# Onion-Omega2-BLE-Pro-Expansion.net
KiCad netlist of a schematic drawn in EAGLE
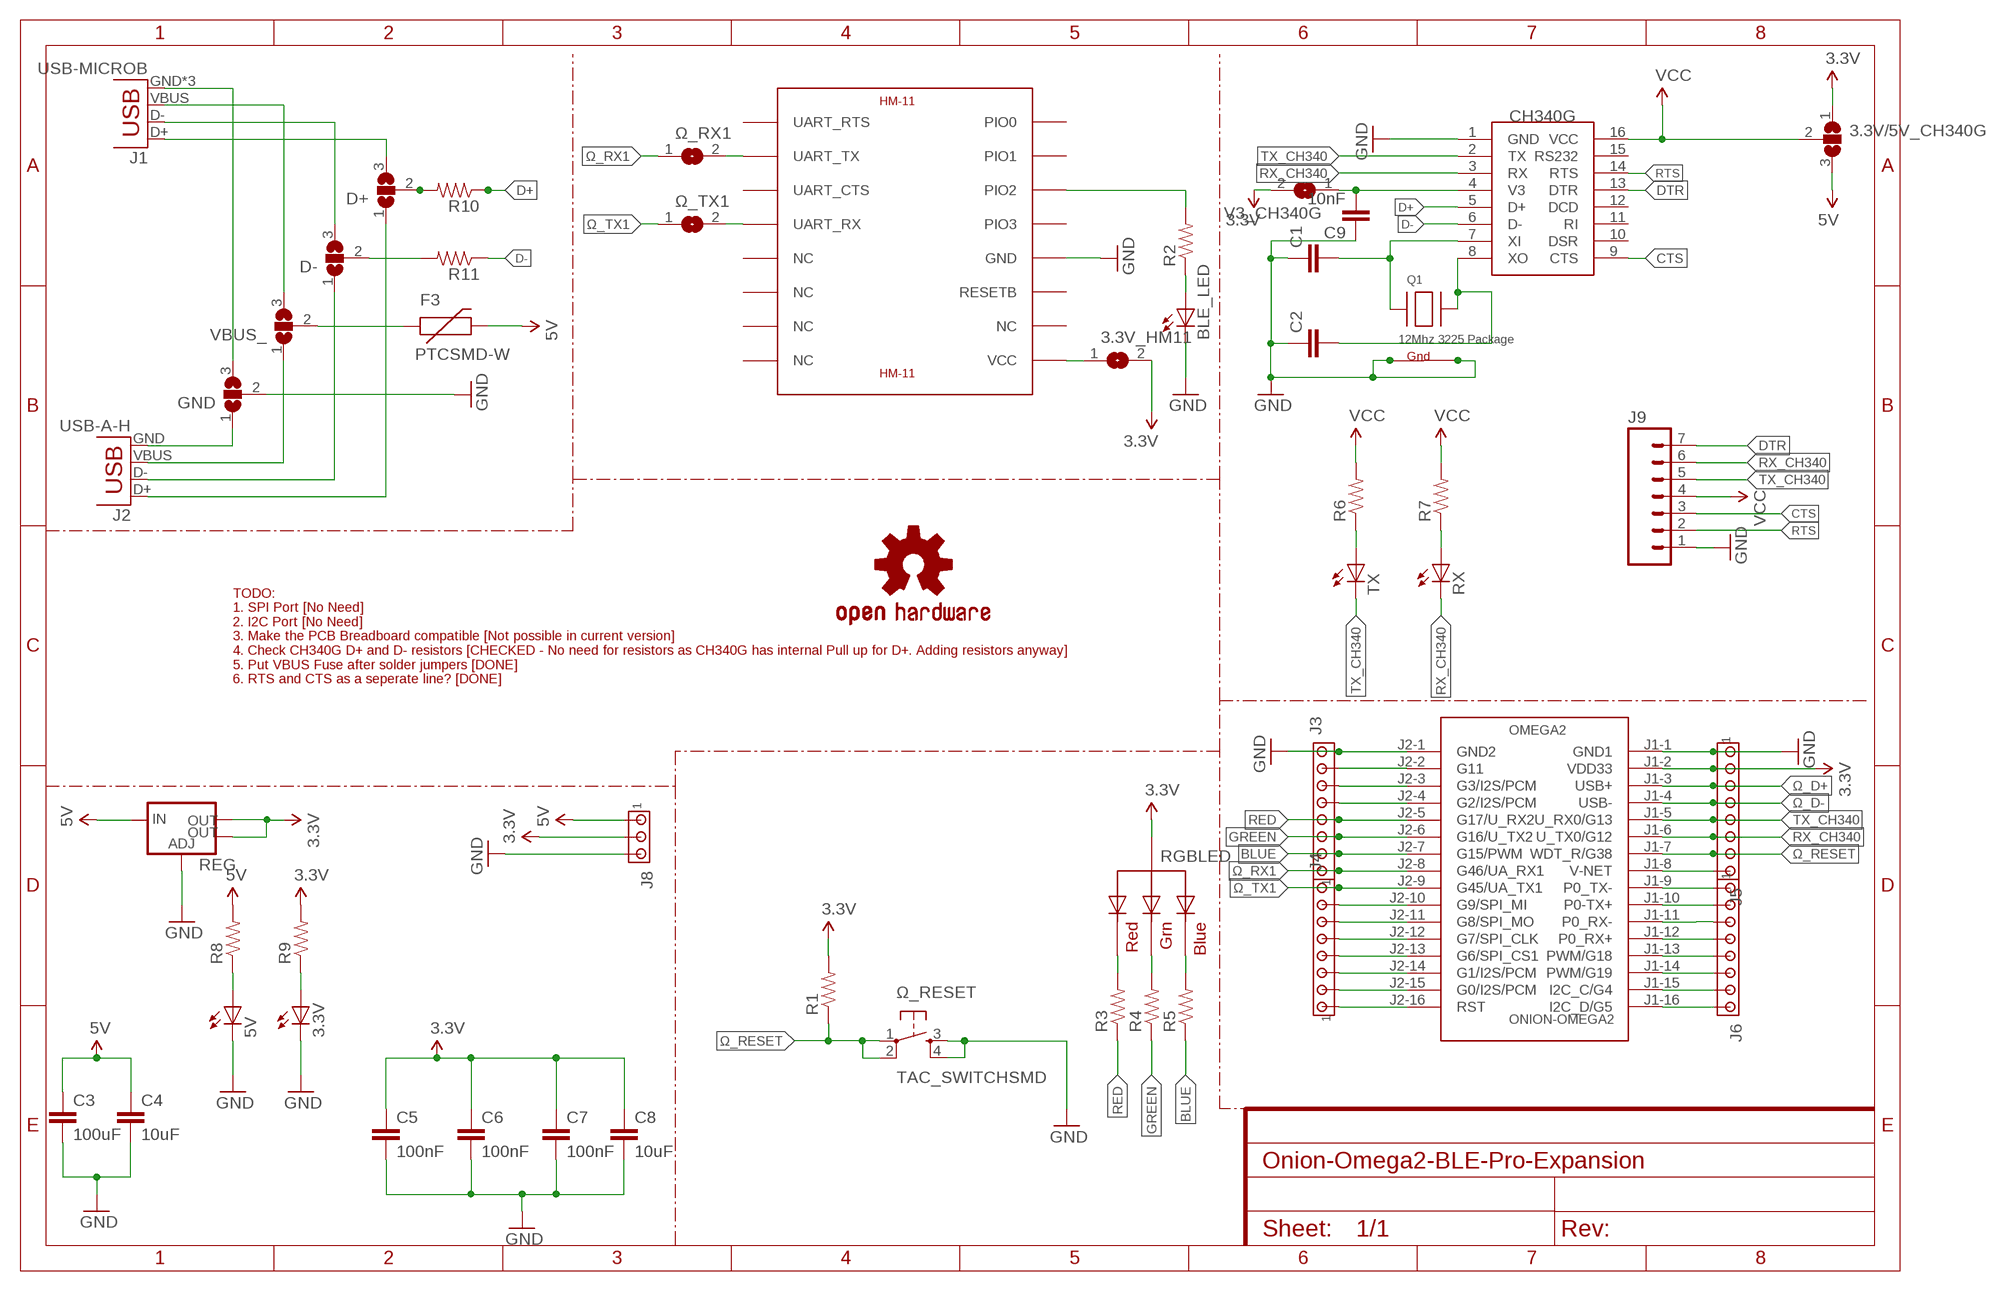
[diagram p0: schematic, sheet 1]

(export (version "E")
  (design (tool "Eeschema 10.0.6"))
  (components
    (comp (ref "3.3V")
      (value "LEDCHIPLED_1206")
      (footprint "eagle-import:CHIPLED_1206")
      (libsource (lib "eagle-import") (part "LEDCHIPLED_1206"))
    )
    (comp (ref "3.3V/5V_CH340G")
      (value "SJ2W")
      (footprint "eagle-import:SJ_2")
      (libsource (lib "eagle-import") (part "SJ2W"))
    )
    (comp (ref "3.3V_HM11")
      (value "SJ")
      (footprint "eagle-import:SJ")
      (libsource (lib "eagle-import") (part "SJ"))
    )
    (comp (ref "5V")
      (value "LEDCHIPLED_1206")
      (footprint "eagle-import:CHIPLED_1206")
      (libsource (lib "eagle-import") (part "LEDCHIPLED_1206"))
    )
    (comp (ref "BLE_LED")
      (value "LEDCHIPLED_1206")
      (footprint "eagle-import:CHIPLED_1206")
      (libsource (lib "eagle-import") (part "LEDCHIPLED_1206"))
    )
    (comp (ref "C1")
      (value "CAP1206")
      (footprint "eagle-import:1206")
      (libsource (lib "eagle-import") (part "CAP1206"))
    )
    (comp (ref "C2")
      (value "CAP1206")
      (footprint "eagle-import:1206")
      (libsource (lib "eagle-import") (part "CAP1206"))
    )
    (comp (ref "C3")
      (value "100uF")
      (footprint "eagle-import:1206")
      (libsource (lib "eagle-import") (part "CAP1206"))
    )
    (comp (ref "C4")
      (value "10uF")
      (footprint "eagle-import:1206")
      (libsource (lib "eagle-import") (part "CAP1206"))
    )
    (comp (ref "C5")
      (value "100nF")
      (footprint "eagle-import:1206")
      (libsource (lib "eagle-import") (part "CAP1206"))
    )
    (comp (ref "C6")
      (value "100nF")
      (footprint "eagle-import:1206")
      (libsource (lib "eagle-import") (part "CAP1206"))
    )
    (comp (ref "C7")
      (value "100nF")
      (footprint "eagle-import:1206")
      (libsource (lib "eagle-import") (part "CAP1206"))
    )
    (comp (ref "C8")
      (value "10uF")
      (footprint "eagle-import:1206")
      (libsource (lib "eagle-import") (part "CAP1206"))
    )
    (comp (ref "C9")
      (value "10nF")
      (footprint "eagle-import:1206")
      (libsource (lib "eagle-import") (part "CAP1206"))
    )
    (comp (ref "D+")
      (value "SJ2W")
      (footprint "eagle-import:SJ_2")
      (libsource (lib "eagle-import") (part "SJ2W"))
    )
    (comp (ref "D-")
      (value "SJ2W")
      (footprint "eagle-import:SJ_2")
      (libsource (lib "eagle-import") (part "SJ2W"))
    )
    (comp (ref "F3")
      (value "PTCSMD-W")
      (footprint "eagle-import:PTC-1206-WIDE")
      (libsource (lib "eagle-import") (part "PTCSMD-W"))
    )
    (comp (ref "GND")
      (value "SJ2W")
      (footprint "eagle-import:SJ_2")
      (libsource (lib "eagle-import") (part "SJ2W"))
    )
    (comp (ref "J1")
      (value "USB-MICROB")
      (footprint "eagle-import:USB-MICROB")
      (libsource (lib "eagle-import") (part "USB-MICROB"))
    )
    (comp (ref "J2")
      (value "USB-A-H")
      (footprint "eagle-import:USB-A-H")
      (libsource (lib "eagle-import") (part "USB-A-H"))
    )
    (comp (ref "J3")
      (value "MTA08-100")
      (footprint "eagle-import:10X08MTA")
      (libsource (lib "eagle-import") (part "MTA08-100"))
    )
    (comp (ref "J4")
      (value "MTA08-100")
      (footprint "eagle-import:10X08MTA")
      (libsource (lib "eagle-import") (part "MTA08-100"))
    )
    (comp (ref "J5")
      (value "MTA08-100")
      (footprint "eagle-import:10X08MTA")
      (libsource (lib "eagle-import") (part "MTA08-100"))
    )
    (comp (ref "J6")
      (value "MTA08-100")
      (footprint "eagle-import:10X08MTA")
      (libsource (lib "eagle-import") (part "MTA08-100"))
    )
    (comp (ref "J8")
      (value "MTA03-100")
      (footprint "eagle-import:10X03MTA")
      (libsource (lib "eagle-import") (part "MTA03-100"))
    )
    (comp (ref "J9")
      (value "M07SMD")
      (footprint "eagle-import:1X07-SMD-FEMALE-V2")
      (libsource (lib "eagle-import") (part "M07SMD"))
    )
    (comp (ref "LOGO1")
      (value "OSHW-LOGOMINI")
      (footprint "eagle-import:OSHW-LOGO-MINI")
      (libsource (lib "eagle-import") (part "OSHW-LOGOMINI"))
    )
    (comp (ref "OMEGA2")
      (value "ONION-OMEGA2")
      (footprint "eagle-import:ONION-2MM-2X16")
      (libsource (lib "eagle-import") (part "ONION-OMEGA2"))
    )
    (comp (ref "Q1")
      (value "12Mhz 3225 Package")
      (footprint "eagle-import:NX3225")
      (libsource (lib "eagle-import") (part "XTAL-4-3225"))
    )
    (comp (ref "R1")
      (value "RESISTOR1206")
      (footprint "eagle-import:1206")
      (libsource (lib "eagle-import") (part "RESISTOR1206"))
    )
    (comp (ref "R2")
      (value "RESISTOR1206")
      (footprint "eagle-import:1206")
      (libsource (lib "eagle-import") (part "RESISTOR1206"))
    )
    (comp (ref "R3")
      (value "RESISTOR1206")
      (footprint "eagle-import:1206")
      (libsource (lib "eagle-import") (part "RESISTOR1206"))
    )
    (comp (ref "R4")
      (value "RESISTOR1206")
      (footprint "eagle-import:1206")
      (libsource (lib "eagle-import") (part "RESISTOR1206"))
    )
    (comp (ref "R5")
      (value "RESISTOR1206")
      (footprint "eagle-import:1206")
      (libsource (lib "eagle-import") (part "RESISTOR1206"))
    )
    (comp (ref "R6")
      (value "RESISTOR1206")
      (footprint "eagle-import:1206")
      (libsource (lib "eagle-import") (part "RESISTOR1206"))
    )
    (comp (ref "R7")
      (value "RESISTOR1206")
      (footprint "eagle-import:1206")
      (libsource (lib "eagle-import") (part "RESISTOR1206"))
    )
    (comp (ref "R8")
      (value "RESISTOR1206")
      (footprint "eagle-import:1206")
      (libsource (lib "eagle-import") (part "RESISTOR1206"))
    )
    (comp (ref "R9")
      (value "RESISTOR1206")
      (footprint "eagle-import:1206")
      (libsource (lib "eagle-import") (part "RESISTOR1206"))
    )
    (comp (ref "R10")
      (value "RESISTOR0805-RES")
      (footprint "eagle-import:0805")
      (libsource (lib "eagle-import") (part "RESISTOR0805-RES"))
    )
    (comp (ref "R11")
      (value "RESISTOR0805-RES")
      (footprint "eagle-import:0805")
      (libsource (lib "eagle-import") (part "RESISTOR0805-RES"))
    )
    (comp (ref "REG")
      (value "V_REG_LM1117SOT223")
      (footprint "eagle-import:SOT223")
      (libsource (lib "eagle-import") (part "V_REG_LM1117SOT223"))
    )
    (comp (ref "RGBLED")
      (value "RGBLED_CA-PIRANHA")
      (footprint "eagle-import:PIRANHA5MM")
      (libsource (lib "eagle-import") (part "RGBLED_CA-PIRANHA"))
    )
    (comp (ref "RX")
      (value "LEDCHIPLED_1206")
      (footprint "eagle-import:CHIPLED_1206")
      (libsource (lib "eagle-import") (part "LEDCHIPLED_1206"))
    )
    (comp (ref "TX")
      (value "LEDCHIPLED_1206")
      (footprint "eagle-import:CHIPLED_1206")
      (libsource (lib "eagle-import") (part "LEDCHIPLED_1206"))
    )
    (comp (ref "U$1")
      (value "CH340G")
      (footprint "eagle-import:SOIC16")
      (libsource (lib "eagle-import") (part "CH340G"))
    )
    (comp (ref "U$2")
      (value "HM-11")
      (footprint "eagle-import:HM-11")
      (libsource (lib "eagle-import") (part "HM-11"))
    )
    (comp (ref "V3_CH340G")
      (value "SJ")
      (footprint "eagle-import:SJ")
      (libsource (lib "eagle-import") (part "SJ"))
    )
    (comp (ref "VBUS_")
      (value "SJ2W")
      (footprint "eagle-import:SJ_2")
      (libsource (lib "eagle-import") (part "SJ2W"))
    )
    (comp (ref "Ω_RESET")
      (value "TAC_SWITCHSMD")
      (footprint "eagle-import:TACTILE-SWITCH-SMD")
      (libsource (lib "eagle-import") (part "TAC_SWITCHSMD"))
    )
    (comp (ref "Ω_RX1")
      (value "SJ")
      (footprint "eagle-import:SJ")
      (libsource (lib "eagle-import") (part "SJ"))
    )
    (comp (ref "Ω_TX1")
      (value "SJ")
      (footprint "eagle-import:SJ")
      (libsource (lib "eagle-import") (part "SJ"))
    )
  )
  (nets
    (net (code "1") (name "3.3V") (class "Default")
      (node (ref "3.3V/5V_CH340G") (pin "1") (pinfunction "1_1") (pintype "passive"))
      (node (ref "3.3V_HM11") (pin "2") (pinfunction "2_2") (pintype "passive"))
      (node (ref "C5") (pin "1") (pinfunction "1_1") (pintype "passive"))
      (node (ref "C6") (pin "1") (pinfunction "1_1") (pintype "passive"))
      (node (ref "C7") (pin "1") (pinfunction "1_1") (pintype "passive"))
      (node (ref "C8") (pin "1") (pinfunction "1_1") (pintype "passive"))
      (node (ref "J5") (pin "2") (pinfunction "2_2") (pintype "passive"))
      (node (ref "J8") (pin "2") (pinfunction "2_2") (pintype "passive"))
      (node (ref "OMEGA2") (pin "J1-2") (pinfunction "VDD33_J1-2") (pintype "bidirectional"))
      (node (ref "R1") (pin "2") (pinfunction "2_2") (pintype "passive"))
      (node (ref "R9") (pin "2") (pinfunction "2_2") (pintype "passive"))
      (node (ref "REG") (pin "2") (pinfunction "OUT_2") (pintype "output"))
      (node (ref "REG") (pin "4") (pinfunction "OUT_4") (pintype "output"))
      (node (ref "RGBLED") (pin "4") (pinfunction "VCC_4") (pintype "bidirectional"))
      (node (ref "V3_CH340G") (pin "2") (pinfunction "2_2") (pintype "passive"))
    )
    (net (code "2") (name "5V") (class "Default")
      (node (ref "3.3V/5V_CH340G") (pin "3") (pinfunction "3_3") (pintype "passive"))
      (node (ref "C3") (pin "1") (pinfunction "1_1") (pintype "passive"))
      (node (ref "C4") (pin "1") (pinfunction "1_1") (pintype "passive"))
      (node (ref "F3") (pin "2") (pinfunction "2_2") (pintype "bidirectional"))
      (node (ref "J8") (pin "1") (pinfunction "1_1") (pintype "passive"))
      (node (ref "R8") (pin "2") (pinfunction "2_2") (pintype "passive"))
      (node (ref "REG") (pin "3") (pinfunction "IN_3") (pintype "input"))
    )
    (net (code "3") (name "BLUE") (class "Default")
      (node (ref "J3") (pin "2") (pinfunction "2_2") (pintype "passive"))
      (node (ref "OMEGA2") (pin "J2-7") (pinfunction "G15/PWM_J2-7") (pintype "bidirectional"))
      (node (ref "R5") (pin "1") (pinfunction "1_1") (pintype "passive"))
    )
    (net (code "4") (name "CTS") (class "Default")
      (node (ref "J9") (pin "3") (pinfunction "3_3") (pintype "passive"))
      (node (ref "U$1") (pin "9") (pinfunction "CTS_9") (pintype "bidirectional"))
    )
    (net (code "5") (name "D+") (class "Default")
      (node (ref "R10") (pin "1") (pinfunction "1_1") (pintype "passive"))
      (node (ref "U$1") (pin "5") (pinfunction "D+_5") (pintype "bidirectional"))
    )
    (net (code "6") (name "D-") (class "Default")
      (node (ref "R11") (pin "1") (pinfunction "1_1") (pintype "passive"))
      (node (ref "U$1") (pin "6") (pinfunction "D-_6") (pintype "bidirectional"))
    )
    (net (code "7") (name "DTR") (class "Default")
      (node (ref "J9") (pin "7") (pinfunction "7_7") (pintype "passive"))
      (node (ref "U$1") (pin "13") (pinfunction "DTR_13") (pintype "bidirectional"))
    )
    (net (code "8") (name "GND") (class "Default")
      (node (ref "3.3V") (pin "C") (pinfunction "C_C") (pintype "passive"))
      (node (ref "5V") (pin "C") (pinfunction "C_C") (pintype "passive"))
      (node (ref "BLE_LED") (pin "C") (pinfunction "C_C") (pintype "passive"))
      (node (ref "C1") (pin "1") (pinfunction "1_1") (pintype "passive"))
      (node (ref "C2") (pin "1") (pinfunction "1_1") (pintype "passive"))
      (node (ref "C3") (pin "2") (pinfunction "2_2") (pintype "passive"))
      (node (ref "C4") (pin "2") (pinfunction "2_2") (pintype "passive"))
      (node (ref "C5") (pin "2") (pinfunction "2_2") (pintype "passive"))
      (node (ref "C6") (pin "2") (pinfunction "2_2") (pintype "passive"))
      (node (ref "C7") (pin "2") (pinfunction "2_2") (pintype "passive"))
      (node (ref "C8") (pin "2") (pinfunction "2_2") (pintype "passive"))
      (node (ref "C9") (pin "1") (pinfunction "1_1") (pintype "passive"))
      (node (ref "GND") (pin "2") (pinfunction "2_2") (pintype "passive"))
      (node (ref "J3") (pin "8") (pinfunction "8_8") (pintype "passive"))
      (node (ref "J5") (pin "1") (pinfunction "1_1") (pintype "passive"))
      (node (ref "J8") (pin "3") (pinfunction "3_3") (pintype "passive"))
      (node (ref "J9") (pin "1") (pinfunction "1_1") (pintype "passive"))
      (node (ref "OMEGA2") (pin "J1-1") (pinfunction "GND1_J1-1") (pintype "bidirectional"))
      (node (ref "OMEGA2") (pin "J2-1") (pinfunction "GND2_J2-1") (pintype "bidirectional"))
      (node (ref "Q1") (pin "2") (pinfunction "G2_2") (pintype "power_in"))
      (node (ref "Q1") (pin "4") (pinfunction "G1_4") (pintype "power_in"))
      (node (ref "REG") (pin "1") (pinfunction "ADJ_1") (pintype "input"))
      (node (ref "U$1") (pin "1") (pinfunction "GND_1") (pintype "bidirectional"))
      (node (ref "U$2") (pin "GND") (pinfunction "GND_GND") (pintype "bidirectional"))
      (node (ref "Ω_RESET") (pin "3") (pinfunction "3_3") (pintype "passive"))
      (node (ref "Ω_RESET") (pin "4") (pinfunction "4_4") (pintype "passive"))
    )
    (net (code "9") (name "GREEN") (class "Default")
      (node (ref "J3") (pin "3") (pinfunction "3_3") (pintype "passive"))
      (node (ref "OMEGA2") (pin "J2-6") (pinfunction "G16/U_TX2_J2-6") (pintype "bidirectional"))
      (node (ref "R4") (pin "1") (pinfunction "1_1") (pintype "passive"))
    )
    (net (code "10") (name "Net-(3.3V-PadA)") (class "Default")
      (node (ref "3.3V") (pin "A") (pinfunction "A_A") (pintype "passive"))
      (node (ref "R9") (pin "1") (pinfunction "1_1") (pintype "passive"))
    )
    (net (code "11") (name "Net-(3.3V_HM11-Pad1)") (class "Default")
      (node (ref "3.3V_HM11") (pin "1") (pinfunction "1_1") (pintype "passive"))
      (node (ref "U$2") (pin "VCC") (pinfunction "VCC_VCC") (pintype "bidirectional"))
    )
    (net (code "12") (name "Net-(5V-PadA)") (class "Default")
      (node (ref "5V") (pin "A") (pinfunction "A_A") (pintype "passive"))
      (node (ref "R8") (pin "1") (pinfunction "1_1") (pintype "passive"))
    )
    (net (code "13") (name "Net-(BLE_LED-PadA)") (class "Default")
      (node (ref "BLE_LED") (pin "A") (pinfunction "A_A") (pintype "passive"))
      (node (ref "R2") (pin "1") (pinfunction "1_1") (pintype "passive"))
    )
    (net (code "14") (name "Net-(D+-Pad1)") (class "Default")
      (node (ref "D+") (pin "1") (pinfunction "1_1") (pintype "passive"))
      (node (ref "J2") (pin "D+") (pinfunction "D+_D+") (pintype "bidirectional"))
    )
    (net (code "15") (name "Net-(D+-Pad2)") (class "Default")
      (node (ref "D+") (pin "2") (pinfunction "2_2") (pintype "passive"))
      (node (ref "R10") (pin "2") (pinfunction "2_2") (pintype "passive"))
    )
    (net (code "16") (name "Net-(D+-Pad3)") (class "Default")
      (node (ref "D+") (pin "3") (pinfunction "3_3") (pintype "passive"))
      (node (ref "J1") (pin "D+") (pinfunction "D+_D+") (pintype "bidirectional"))
    )
    (net (code "17") (name "Net-(D--Pad1)") (class "Default")
      (node (ref "D-") (pin "1") (pinfunction "1_1") (pintype "passive"))
      (node (ref "J2") (pin "D-") (pinfunction "D-_D-") (pintype "bidirectional"))
    )
    (net (code "18") (name "Net-(D--Pad2)") (class "Default")
      (node (ref "D-") (pin "2") (pinfunction "2_2") (pintype "passive"))
      (node (ref "R11") (pin "2") (pinfunction "2_2") (pintype "passive"))
    )
    (net (code "19") (name "Net-(D--Pad3)") (class "Default")
      (node (ref "D-") (pin "3") (pinfunction "3_3") (pintype "passive"))
      (node (ref "J1") (pin "D-") (pinfunction "D-_D-") (pintype "bidirectional"))
    )
    (net (code "20") (name "Net-(F3-Pad1)") (class "Default")
      (node (ref "F3") (pin "1") (pinfunction "1_1") (pintype "bidirectional"))
      (node (ref "VBUS_") (pin "2") (pinfunction "2_2") (pintype "passive"))
    )
    (net (code "21") (name "Net-(GND-Pad1)") (class "Default")
      (node (ref "GND") (pin "1") (pinfunction "1_1") (pintype "passive"))
      (node (ref "J2") (pin "GND") (pinfunction "GND_GND") (pintype "bidirectional"))
    )
    (net (code "22") (name "Net-(GND-Pad3)") (class "Default")
      (node (ref "GND") (pin "3") (pinfunction "3_3") (pintype "passive"))
      (node (ref "J1") (pin "GND") (pinfunction "GND_GND") (pintype "bidirectional"))
      (node (ref "J1") (pin "MT1") (pinfunction "GND_MT1") (pintype "bidirectional"))
      (node (ref "J1") (pin "MT2") (pinfunction "GND_MT2") (pintype "bidirectional"))
    )
    (net (code "23") (name "Net-(J1-PadVBUS)") (class "Default")
      (node (ref "J1") (pin "VBUS") (pinfunction "VBUS_VBUS") (pintype "bidirectional"))
      (node (ref "VBUS_") (pin "3") (pinfunction "3_3") (pintype "passive"))
    )
    (net (code "24") (name "Net-(J2-PadVBUS)") (class "Default")
      (node (ref "J2") (pin "VBUS") (pinfunction "VBUS_VBUS") (pintype "bidirectional"))
      (node (ref "VBUS_") (pin "1") (pinfunction "1_1") (pintype "passive"))
    )
    (net (code "25") (name "Net-(OMEGA2-G0{slash}I2S{slash}PCM)") (class "Default")
      (node (ref "J4") (pin "2") (pinfunction "2_2") (pintype "passive"))
      (node (ref "OMEGA2") (pin "J2-15") (pinfunction "G0/I2S/PCM_J2-15") (pintype "bidirectional"))
    )
    (net (code "26") (name "Net-(OMEGA2-G1{slash}I2S{slash}PCM)") (class "Default")
      (node (ref "J4") (pin "3") (pinfunction "3_3") (pintype "passive"))
      (node (ref "OMEGA2") (pin "J2-14") (pinfunction "G1/I2S/PCM_J2-14") (pintype "bidirectional"))
    )
    (net (code "27") (name "Net-(OMEGA2-G2{slash}I2S{slash}PCM)") (class "Default")
      (node (ref "J3") (pin "5") (pinfunction "5_5") (pintype "passive"))
      (node (ref "OMEGA2") (pin "J2-4") (pinfunction "G2/I2S/PCM_J2-4") (pintype "bidirectional"))
    )
    (net (code "28") (name "Net-(OMEGA2-G3{slash}I2S{slash}PCM)") (class "Default")
      (node (ref "J3") (pin "6") (pinfunction "6_6") (pintype "passive"))
      (node (ref "OMEGA2") (pin "J2-3") (pinfunction "G3/I2S/PCM_J2-3") (pintype "bidirectional"))
    )
    (net (code "29") (name "Net-(OMEGA2-G6{slash}SPI_CS1)") (class "Default")
      (node (ref "J4") (pin "4") (pinfunction "4_4") (pintype "passive"))
      (node (ref "OMEGA2") (pin "J2-13") (pinfunction "G6/SPI_CS1_J2-13") (pintype "bidirectional"))
    )
    (net (code "30") (name "Net-(OMEGA2-G7{slash}SPI_CLK)") (class "Default")
      (node (ref "J4") (pin "5") (pinfunction "5_5") (pintype "passive"))
      (node (ref "OMEGA2") (pin "J2-12") (pinfunction "G7/SPI_CLK_J2-12") (pintype "bidirectional"))
    )
    (net (code "31") (name "Net-(OMEGA2-G8{slash}SPI_MO)") (class "Default")
      (node (ref "J4") (pin "6") (pinfunction "6_6") (pintype "passive"))
      (node (ref "OMEGA2") (pin "J2-11") (pinfunction "G8/SPI_MO_J2-11") (pintype "bidirectional"))
    )
    (net (code "32") (name "Net-(OMEGA2-G9{slash}SPI_MI)") (class "Default")
      (node (ref "J4") (pin "7") (pinfunction "7_7") (pintype "passive"))
      (node (ref "OMEGA2") (pin "J2-10") (pinfunction "G9/SPI_MI_J2-10") (pintype "bidirectional"))
    )
    (net (code "33") (name "Net-(OMEGA2-G11)") (class "Default")
      (node (ref "J3") (pin "7") (pinfunction "7_7") (pintype "passive"))
      (node (ref "OMEGA2") (pin "J2-2") (pinfunction "G11_J2-2") (pintype "bidirectional"))
    )
    (net (code "34") (name "Net-(OMEGA2-I2C_C{slash}G4)") (class "Default")
      (node (ref "J6") (pin "7") (pinfunction "7_7") (pintype "passive"))
      (node (ref "OMEGA2") (pin "J1-15") (pinfunction "I2C_C/G4_J1-15") (pintype "bidirectional"))
    )
    (net (code "35") (name "Net-(OMEGA2-I2C_D{slash}G5)") (class "Default")
      (node (ref "J6") (pin "8") (pinfunction "8_8") (pintype "passive"))
      (node (ref "OMEGA2") (pin "J1-16") (pinfunction "I2C_D/G5_J1-16") (pintype "bidirectional"))
    )
    (net (code "36") (name "Net-(OMEGA2-P0-TX+)") (class "Default")
      (node (ref "J6") (pin "2") (pinfunction "2_2") (pintype "passive"))
      (node (ref "OMEGA2") (pin "J1-10") (pinfunction "P0-TX+_J1-10") (pintype "bidirectional"))
    )
    (net (code "37") (name "Net-(OMEGA2-P0_RX+)") (class "Default")
      (node (ref "J6") (pin "4") (pinfunction "4_4") (pintype "passive"))
      (node (ref "OMEGA2") (pin "J1-12") (pinfunction "P0_RX+_J1-12") (pintype "bidirectional"))
    )
    (net (code "38") (name "Net-(OMEGA2-P0_RX-)") (class "Default")
      (node (ref "J6") (pin "3") (pinfunction "3_3") (pintype "passive"))
      (node (ref "OMEGA2") (pin "J1-11") (pinfunction "P0_RX-_J1-11") (pintype "bidirectional"))
    )
    (net (code "39") (name "Net-(OMEGA2-P0_TX-)") (class "Default")
      (node (ref "J6") (pin "1") (pinfunction "1_1") (pintype "passive"))
      (node (ref "OMEGA2") (pin "J1-9") (pinfunction "P0_TX-_J1-9") (pintype "bidirectional"))
    )
    (net (code "40") (name "Net-(OMEGA2-PWM{slash}G18)") (class "Default")
      (node (ref "J6") (pin "5") (pinfunction "5_5") (pintype "passive"))
      (node (ref "OMEGA2") (pin "J1-13") (pinfunction "PWM/G18_J1-13") (pintype "bidirectional"))
    )
    (net (code "41") (name "Net-(OMEGA2-PWM{slash}G19)") (class "Default")
      (node (ref "J6") (pin "6") (pinfunction "6_6") (pintype "passive"))
      (node (ref "OMEGA2") (pin "J1-14") (pinfunction "PWM/G19_J1-14") (pintype "bidirectional"))
    )
    (net (code "42") (name "Net-(OMEGA2-RST)") (class "Default")
      (node (ref "J4") (pin "1") (pinfunction "1_1") (pintype "passive"))
      (node (ref "OMEGA2") (pin "J2-16") (pinfunction "RST_J2-16") (pintype "bidirectional"))
    )
    (net (code "43") (name "Net-(OMEGA2-V-NET)") (class "Default")
      (node (ref "J5") (pin "8") (pinfunction "8_8") (pintype "passive"))
      (node (ref "OMEGA2") (pin "J1-8") (pinfunction "V-NET_J1-8") (pintype "bidirectional"))
    )
    (net (code "44") (name "Net-(Q1-X1)") (class "Default")
      (node (ref "C1") (pin "2") (pinfunction "2_2") (pintype "passive"))
      (node (ref "Q1") (pin "1") (pinfunction "X1_1") (pintype "bidirectional"))
      (node (ref "U$1") (pin "7") (pinfunction "XI_7") (pintype "bidirectional"))
    )
    (net (code "45") (name "Net-(Q1-X2)") (class "Default")
      (node (ref "C2") (pin "2") (pinfunction "2_2") (pintype "passive"))
      (node (ref "Q1") (pin "3") (pinfunction "X2_3") (pintype "bidirectional"))
      (node (ref "U$1") (pin "8") (pinfunction "XO_8") (pintype "bidirectional"))
    )
    (net (code "46") (name "Net-(R2-Pad2)") (class "Default")
      (node (ref "R2") (pin "2") (pinfunction "2_2") (pintype "passive"))
      (node (ref "U$2") (pin "PIO2") (pinfunction "PIO2_PIO2") (pintype "bidirectional"))
    )
    (net (code "47") (name "Net-(R6-Pad1)") (class "Default")
      (node (ref "R6") (pin "1") (pinfunction "1_1") (pintype "passive"))
      (node (ref "TX") (pin "A") (pinfunction "A_A") (pintype "passive"))
    )
    (net (code "48") (name "Net-(R7-Pad1)") (class "Default")
      (node (ref "R7") (pin "1") (pinfunction "1_1") (pintype "passive"))
      (node (ref "RX") (pin "A") (pinfunction "A_A") (pintype "passive"))
    )
    (net (code "49") (name "Net-(RGBLED-BLUE)") (class "Default")
      (node (ref "R5") (pin "2") (pinfunction "2_2") (pintype "passive"))
      (node (ref "RGBLED") (pin "1") (pinfunction "BLUE_1") (pintype "bidirectional"))
    )
    (net (code "50") (name "Net-(RGBLED-GREEN)") (class "Default")
      (node (ref "R4") (pin "2") (pinfunction "2_2") (pintype "passive"))
      (node (ref "RGBLED") (pin "3") (pinfunction "GREEN_3") (pintype "bidirectional"))
    )
    (net (code "51") (name "Net-(RGBLED-RED)") (class "Default")
      (node (ref "R3") (pin "2") (pinfunction "2_2") (pintype "passive"))
      (node (ref "RGBLED") (pin "2") (pinfunction "RED_2") (pintype "bidirectional"))
    )
    (net (code "52") (name "Net-(U$1-V3)") (class "Default")
      (node (ref "C9") (pin "2") (pinfunction "2_2") (pintype "passive"))
      (node (ref "U$1") (pin "4") (pinfunction "V3_4") (pintype "bidirectional"))
      (node (ref "V3_CH340G") (pin "1") (pinfunction "1_1") (pintype "passive"))
    )
    (net (code "53") (name "Net-(U$2-PadUART_RX)") (class "Default")
      (node (ref "U$2") (pin "UART_RX") (pinfunction "UART_RX_UART_RX") (pintype "bidirectional"))
      (node (ref "Ω_TX1") (pin "2") (pinfunction "2_2") (pintype "passive"))
    )
    (net (code "54") (name "Net-(U$2-PadUART_TX)") (class "Default")
      (node (ref "U$2") (pin "UART_TX") (pinfunction "UART_TX_UART_TX") (pintype "bidirectional"))
      (node (ref "Ω_RX1") (pin "2") (pinfunction "2_2") (pintype "passive"))
    )
    (net (code "55") (name "RED") (class "Default")
      (node (ref "J3") (pin "4") (pinfunction "4_4") (pintype "passive"))
      (node (ref "OMEGA2") (pin "J2-5") (pinfunction "G17/U_RX2_J2-5") (pintype "bidirectional"))
      (node (ref "R3") (pin "1") (pinfunction "1_1") (pintype "passive"))
    )
    (net (code "56") (name "RTS") (class "Default")
      (node (ref "J9") (pin "2") (pinfunction "2_2") (pintype "passive"))
      (node (ref "U$1") (pin "14") (pinfunction "RTS_14") (pintype "bidirectional"))
    )
    (net (code "57") (name "RX_CH340") (class "Default")
      (node (ref "J5") (pin "6") (pinfunction "6_6") (pintype "passive"))
      (node (ref "J9") (pin "6") (pinfunction "6_6") (pintype "passive"))
      (node (ref "OMEGA2") (pin "J1-6") (pinfunction "U_TX0/G12_J1-6") (pintype "bidirectional"))
      (node (ref "RX") (pin "C") (pinfunction "C_C") (pintype "passive"))
      (node (ref "U$1") (pin "3") (pinfunction "RX_3") (pintype "bidirectional"))
    )
    (net (code "58") (name "TX_CH340") (class "Default")
      (node (ref "J5") (pin "5") (pinfunction "5_5") (pintype "passive"))
      (node (ref "J9") (pin "5") (pinfunction "5_5") (pintype "passive"))
      (node (ref "OMEGA2") (pin "J1-5") (pinfunction "U_RX0/G13_J1-5") (pintype "bidirectional"))
      (node (ref "TX") (pin "C") (pinfunction "C_C") (pintype "passive"))
      (node (ref "U$1") (pin "2") (pinfunction "TX_2") (pintype "bidirectional"))
    )
    (net (code "59") (name "VCC") (class "Default")
      (node (ref "3.3V/5V_CH340G") (pin "2") (pinfunction "2_2") (pintype "passive"))
      (node (ref "J9") (pin "4") (pinfunction "4_4") (pintype "passive"))
      (node (ref "R6") (pin "2") (pinfunction "2_2") (pintype "passive"))
      (node (ref "R7") (pin "2") (pinfunction "2_2") (pintype "passive"))
      (node (ref "U$1") (pin "16") (pinfunction "VCC_16") (pintype "bidirectional"))
    )
    (net (code "60") (name "unconnected-(U$1-DCD-Pad12)") (class "Default")
      (node (ref "U$1") (pin "12") (pinfunction "DCD_12") (pintype "bidirectional"))
    )
    (net (code "61") (name "unconnected-(U$1-DSR-Pad10)") (class "Default")
      (node (ref "U$1") (pin "10") (pinfunction "DSR_10") (pintype "bidirectional"))
    )
    (net (code "62") (name "unconnected-(U$1-RI-Pad11)") (class "Default")
      (node (ref "U$1") (pin "11") (pinfunction "RI_11") (pintype "bidirectional"))
    )
    (net (code "63") (name "unconnected-(U$1-RS232-Pad15)") (class "Default")
      (node (ref "U$1") (pin "15") (pinfunction "RS232_15") (pintype "bidirectional"))
    )
    (net (code "64") (name "unconnected-(U$2-NC-PadNC@5)") (class "Default")
      (node (ref "U$2") (pin "NC@5") (pinfunction "NC_NC@5") (pintype "bidirectional"))
    )
    (net (code "65") (name "unconnected-(U$2-NC-PadNC@6)") (class "Default")
      (node (ref "U$2") (pin "NC@6") (pinfunction "NC_NC@6") (pintype "bidirectional"))
    )
    (net (code "66") (name "unconnected-(U$2-NC-PadNC@7)") (class "Default")
      (node (ref "U$2") (pin "NC@7") (pinfunction "NC_NC@7") (pintype "bidirectional"))
    )
    (net (code "67") (name "unconnected-(U$2-NC-PadNC@8)") (class "Default")
      (node (ref "U$2") (pin "NC@8") (pinfunction "NC_NC@8") (pintype "bidirectional"))
    )
    (net (code "68") (name "unconnected-(U$2-NC-PadNC@10)") (class "Default")
      (node (ref "U$2") (pin "NC@10") (pinfunction "NC_NC@10") (pintype "bidirectional"))
    )
    (net (code "69") (name "unconnected-(U$2-PadPIO0)") (class "Default")
      (node (ref "U$2") (pin "PIO0") (pinfunction "PIO0_PIO0") (pintype "bidirectional"))
    )
    (net (code "70") (name "unconnected-(U$2-PadPIO1)") (class "Default")
      (node (ref "U$2") (pin "PIO1") (pinfunction "PIO1_PIO1") (pintype "bidirectional"))
    )
    (net (code "71") (name "unconnected-(U$2-PadPIO3)") (class "Default")
      (node (ref "U$2") (pin "PIO3") (pinfunction "PIO3_PIO3") (pintype "bidirectional"))
    )
    (net (code "72") (name "unconnected-(U$2-PadRESETB)") (class "Default")
      (node (ref "U$2") (pin "RESETB") (pinfunction "RESETB_RESETB") (pintype "bidirectional"))
    )
    (net (code "73") (name "unconnected-(U$2-PadUART_CTS)") (class "Default")
      (node (ref "U$2") (pin "UART_CTS") (pinfunction "UART_CTS_UART_CTS") (pintype "bidirectional"))
    )
    (net (code "74") (name "unconnected-(U$2-PadUART_RTS)") (class "Default")
      (node (ref "U$2") (pin "UART_RTS") (pinfunction "UART_RTS_UART_RTS") (pintype "bidirectional"))
    )
    (net (code "75") (name "Ω_D+") (class "Default")
      (node (ref "J5") (pin "3") (pinfunction "3_3") (pintype "passive"))
      (node (ref "OMEGA2") (pin "J1-3") (pinfunction "USB+_J1-3") (pintype "bidirectional"))
    )
    (net (code "76") (name "Ω_D-") (class "Default")
      (node (ref "J5") (pin "4") (pinfunction "4_4") (pintype "passive"))
      (node (ref "OMEGA2") (pin "J1-4") (pinfunction "USB-_J1-4") (pintype "bidirectional"))
    )
    (net (code "77") (name "Ω_RESET") (class "Default")
      (node (ref "J5") (pin "7") (pinfunction "7_7") (pintype "passive"))
      (node (ref "OMEGA2") (pin "J1-7") (pinfunction "WDT_R/G38_J1-7") (pintype "bidirectional"))
      (node (ref "R1") (pin "1") (pinfunction "1_1") (pintype "passive"))
      (node (ref "Ω_RESET") (pin "1") (pinfunction "1_1") (pintype "passive"))
      (node (ref "Ω_RESET") (pin "2") (pinfunction "2_2") (pintype "passive"))
    )
    (net (code "78") (name "Ω_RX1") (class "Default")
      (node (ref "J3") (pin "1") (pinfunction "1_1") (pintype "passive"))
      (node (ref "OMEGA2") (pin "J2-8") (pinfunction "G46/UA_RX1_J2-8") (pintype "bidirectional"))
      (node (ref "Ω_RX1") (pin "1") (pinfunction "1_1") (pintype "passive"))
    )
    (net (code "79") (name "Ω_TX1") (class "Default")
      (node (ref "J4") (pin "8") (pinfunction "8_8") (pintype "passive"))
      (node (ref "OMEGA2") (pin "J2-9") (pinfunction "G45/UA_TX1_J2-9") (pintype "bidirectional"))
      (node (ref "Ω_TX1") (pin "1") (pinfunction "1_1") (pintype "passive"))
    )
  )
)
